# Led_Chaser.net
KiCad netlist of a schematic drawn in Altium Designer
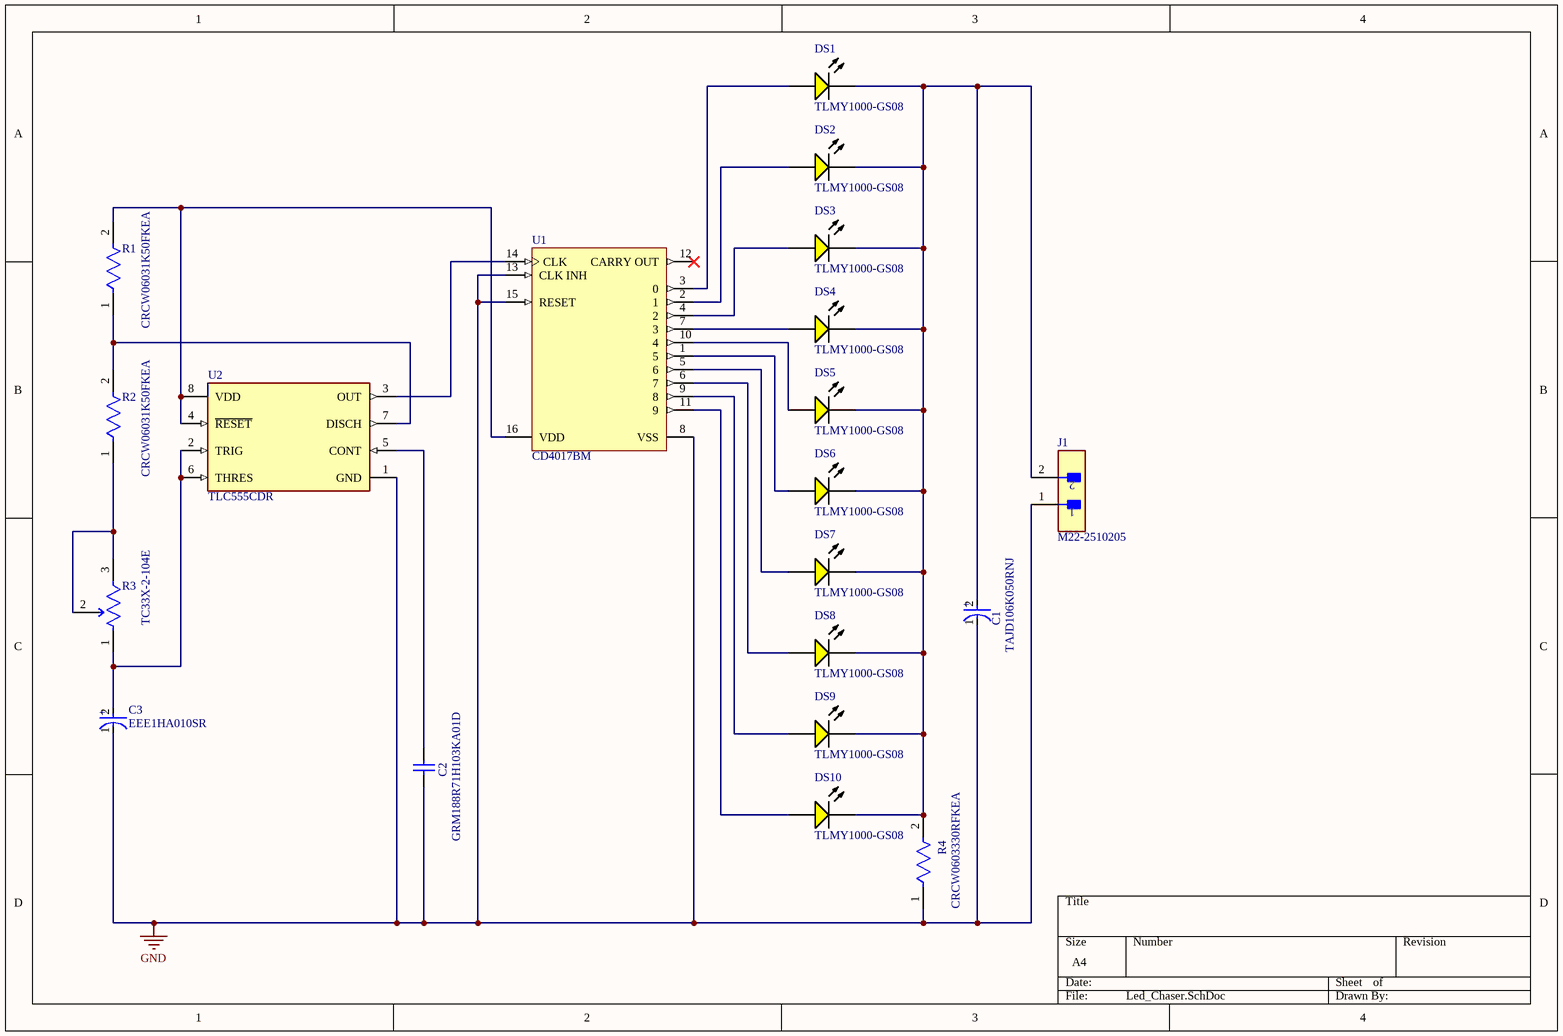
[diagram p0: Led_Chaser.SchDoc]

(export (version "E")
  (design (tool "Eeschema 10.0.6"))
  (components
    (comp (ref "C1")
      (value "TAJD106K050RNJ")
      (footprint "FP-TAJD-MFG")
      (description "10uF 50V  ±10% 800mΩ 2917  SMD Tantalum Capacitor")
      (fields (field (name "VOLTAGE") "50V") (field (name "TOLERANCE") "10%"))
      (libsource (lib "Altium Content Vault") (part "a00bbbee19879c290e62620ae7e47b1"))
    )
    (comp (ref "C2")
      (value "GRM188R71H103KA01D")
      (footprint "CAPC1608X90X35ML10T15")
      (description "Chip Capacitor, 10 nF, +/- 10%, 50 V, -55 to 125 degC, 0603 (1608 Metric), RoHS, Tape and Reel")
      (fields (field (name "VOLTAGE") "50V") (field (name "TOLERANCE") "10%"))
      (libsource (lib "Altium Content Vault") (part "CAP-NP-2"))
    )
    (comp (ref "C3")
      (value "EEE1HA010SR")
      (footprint "FP-SB-MFG")
      (description "CAP ALUM 1UF 20% 50V SMD")
      (fields (field (name "TOLERANCE") "20%") (field (name "VOLTAGE") "50V"))
      (libsource (lib "Altium Content Vault") (part "203bc49f2ac43e59fd269a8c329ed05"))
    )
    (comp (ref "DS1")
      (value "TLMY1000-GS08")
      (footprint "VISH-TLMY1000_V")
      (description "Low Current LED, 40 mW, -40 to 100 degC, 2-Pin SMD, RoHS, Tape and Reel")
      (fields (field (name "MANUFACTURER") "Vishay"))
      (libsource (lib "Altium Content Vault") (part "LED-YELLOW-AK-2"))
    )
    (comp (ref "DS2")
      (value "TLMY1000-GS08")
      (footprint "VISH-TLMY1000_V")
      (description "Low Current LED, 40 mW, -40 to 100 degC, 2-Pin SMD, RoHS, Tape and Reel")
      (fields (field (name "MANUFACTURER") "Vishay"))
      (libsource (lib "Altium Content Vault") (part "LED-YELLOW-AK-2"))
    )
    (comp (ref "DS3")
      (value "TLMY1000-GS08")
      (footprint "VISH-TLMY1000_V")
      (description "Low Current LED, 40 mW, -40 to 100 degC, 2-Pin SMD, RoHS, Tape and Reel")
      (fields (field (name "MANUFACTURER") "Vishay"))
      (libsource (lib "Altium Content Vault") (part "LED-YELLOW-AK-2"))
    )
    (comp (ref "DS4")
      (value "TLMY1000-GS08")
      (footprint "VISH-TLMY1000_V")
      (description "Low Current LED, 40 mW, -40 to 100 degC, 2-Pin SMD, RoHS, Tape and Reel")
      (fields (field (name "MANUFACTURER") "Vishay"))
      (libsource (lib "Altium Content Vault") (part "LED-YELLOW-AK-2"))
    )
    (comp (ref "DS5")
      (value "TLMY1000-GS08")
      (footprint "VISH-TLMY1000_V")
      (description "Low Current LED, 40 mW, -40 to 100 degC, 2-Pin SMD, RoHS, Tape and Reel")
      (fields (field (name "MANUFACTURER") "Vishay"))
      (libsource (lib "Altium Content Vault") (part "LED-YELLOW-AK-2"))
    )
    (comp (ref "DS6")
      (value "TLMY1000-GS08")
      (footprint "VISH-TLMY1000_V")
      (description "Low Current LED, 40 mW, -40 to 100 degC, 2-Pin SMD, RoHS, Tape and Reel")
      (fields (field (name "MANUFACTURER") "Vishay"))
      (libsource (lib "Altium Content Vault") (part "LED-YELLOW-AK-2"))
    )
    (comp (ref "DS7")
      (value "TLMY1000-GS08")
      (footprint "VISH-TLMY1000_V")
      (description "Low Current LED, 40 mW, -40 to 100 degC, 2-Pin SMD, RoHS, Tape and Reel")
      (fields (field (name "MANUFACTURER") "Vishay"))
      (libsource (lib "Altium Content Vault") (part "LED-YELLOW-AK-2"))
    )
    (comp (ref "DS8")
      (value "TLMY1000-GS08")
      (footprint "VISH-TLMY1000_V")
      (description "Low Current LED, 40 mW, -40 to 100 degC, 2-Pin SMD, RoHS, Tape and Reel")
      (fields (field (name "MANUFACTURER") "Vishay"))
      (libsource (lib "Altium Content Vault") (part "LED-YELLOW-AK-2"))
    )
    (comp (ref "DS9")
      (value "TLMY1000-GS08")
      (footprint "VISH-TLMY1000_V")
      (description "Low Current LED, 40 mW, -40 to 100 degC, 2-Pin SMD, RoHS, Tape and Reel")
      (fields (field (name "MANUFACTURER") "Vishay"))
      (libsource (lib "Altium Content Vault") (part "LED-YELLOW-AK-2"))
    )
    (comp (ref "DS10")
      (value "TLMY1000-GS08")
      (footprint "VISH-TLMY1000_V")
      (description "Low Current LED, 40 mW, -40 to 100 degC, 2-Pin SMD, RoHS, Tape and Reel")
      (fields (field (name "MANUFACTURER") "Vishay"))
      (libsource (lib "Altium Content Vault") (part "LED-YELLOW-AK-2"))
    )
    (comp (ref "J1")
      (value "M22-2510205")
      (footprint "FP-M22-2510205-MFG")
      (description "CONN HEADER VERT 2POS 2MM")
      (fields
        (field (name "MANUFACTURER") "Harwin")
        (field (name "OCTOPART") "https://octopart.com/m22-2510205-harwin-2538221")
      )
      (libsource (lib "Altium Content Vault") (part "3bc925449376181038e59eaffc5286c"))
    )
    (comp (ref "R1")
      (value "CRCW06031K50FKEA")
      (footprint "FP-CRCW0603-e3-IPC_A")
      (description "RES Thick Film, 1.5kΩ, 1%, 0.1W, 100ppm/°C, 0603")
      (fields (field (name "TOLERANCE") "1%"))
      (libsource (lib "Altium Content Vault") (part "1029c3af85768c4190bb7ad29bc67b5"))
    )
    (comp (ref "R2")
      (value "CRCW06031K50FKEA")
      (footprint "FP-CRCW0603-e3-IPC_A")
      (description "RES Thick Film, 1.5kΩ, 1%, 0.1W, 100ppm/°C, 0603")
      (fields (field (name "TOLERANCE") "1%"))
      (libsource (lib "Altium Content Vault") (part "1029c3af85768c4190bb7ad29bc67b5"))
    )
    (comp (ref "R3")
      (value "TC33X-2-104E")
      (footprint "FP-TC33X-2-MFG")
      (description "TRIMMER 100K OHM 0.1W J LEAD TOP")
      (fields (field (name "TOLERANCE") "25%"))
      (libsource (lib "Altium Content Vault") (part "13357d81287629c2fd191d242cfa50c"))
    )
    (comp (ref "R4")
      (value "CRCW0603330RFKEA")
      (footprint "FP-CRCW0603-e3-MFG")
      (description "RES Thick Film, 330Ω, 1%, 0.1W, 100ppm/°C, 0603")
      (fields (field (name "TOLERANCE") "1%"))
      (libsource (lib "Altium Content Vault") (part "1029c3af85768c4190bb7ad29bc67b5"))
    )
    (comp (ref "U1")
      (value "CD4017BM")
      (footprint "D0016A_N")
      (description "CMOS Decade Counter with 10 Decoded Outputs, D0016A, TUBE")
      (fields
        (field (name "GENERIC PART NUMBER") "CD4017B")
        (field (name "MANUFACTURER") "Texas Instruments")
      )
      (libsource (lib "Altium Content Vault") (part "TI-CD4017B-16"))
    )
    (comp (ref "U2")
      (value "TLC555CDR")
      (footprint "FP-D0008A-IPC_B")
      (description "IC OSC SGL TIMER 2.1MHZ 8-SOIC")
      (libsource (lib "Altium Content Vault") (part "fd1638d23bf5e420a54176ee4f8e783"))
    )
  )
  (nets
    (net (code "1") (name "GND") (class "Default")
      (node (ref "C1") (pin "1") (pinfunction "C_1") (pintype "passive"))
      (node (ref "C2") (pin "1") (pinfunction "1_1") (pintype "passive"))
      (node (ref "C3") (pin "1") (pinfunction "C_1") (pintype "passive"))
      (node (ref "J1") (pin "1") (pinfunction "1_1") (pintype "passive"))
      (node (ref "R4") (pin "1") (pinfunction "1_1") (pintype "passive"))
      (node (ref "U1") (pin "13") (pinfunction "CLK_INH_13") (pintype "input"))
      (node (ref "U1") (pin "15") (pinfunction "RESET_15") (pintype "input"))
      (node (ref "U1") (pin "8") (pinfunction "VSS_8") (pintype "power_in"))
      (node (ref "U2") (pin "1") (pinfunction "GND_1") (pintype "power_in"))
    )
    (net (code "2") (name "Net-(C1-A)") (class "Default")
      (node (ref "C1") (pin "2") (pinfunction "A_2") (pintype "passive"))
      (node (ref "DS1") (pin "2") (pinfunction "K_2") (pintype "passive"))
      (node (ref "DS10") (pin "2") (pinfunction "K_2") (pintype "passive"))
      (node (ref "DS2") (pin "2") (pinfunction "K_2") (pintype "passive"))
      (node (ref "DS3") (pin "2") (pinfunction "K_2") (pintype "passive"))
      (node (ref "DS4") (pin "2") (pinfunction "K_2") (pintype "passive"))
      (node (ref "DS5") (pin "2") (pinfunction "K_2") (pintype "passive"))
      (node (ref "DS6") (pin "2") (pinfunction "K_2") (pintype "passive"))
      (node (ref "DS7") (pin "2") (pinfunction "K_2") (pintype "passive"))
      (node (ref "DS8") (pin "2") (pinfunction "K_2") (pintype "passive"))
      (node (ref "DS9") (pin "2") (pinfunction "K_2") (pintype "passive"))
      (node (ref "J1") (pin "2") (pinfunction "2_2") (pintype "passive"))
      (node (ref "R4") (pin "2") (pinfunction "2_2") (pintype "passive"))
    )
    (net (code "3") (name "Net-(C3-A)") (class "Default")
      (node (ref "C3") (pin "2") (pinfunction "A_2") (pintype "passive"))
      (node (ref "R3") (pin "1") (pinfunction "CCW_1") (pintype "passive"))
      (node (ref "U2") (pin "2") (pinfunction "TRIG_2") (pintype "input"))
      (node (ref "U2") (pin "6") (pinfunction "THRES_6") (pintype "input"))
    )
    (net (code "4") (name "Net-(DS1-A)") (class "Default")
      (node (ref "DS1") (pin "1") (pinfunction "A_1") (pintype "passive"))
      (node (ref "U1") (pin "3") (pinfunction "0_3") (pintype "output"))
    )
    (net (code "5") (name "Net-(DS2-A)") (class "Default")
      (node (ref "DS2") (pin "1") (pinfunction "A_1") (pintype "passive"))
      (node (ref "U1") (pin "2") (pinfunction "1_2") (pintype "output"))
    )
    (net (code "6") (name "Net-(DS3-A)") (class "Default")
      (node (ref "DS3") (pin "1") (pinfunction "A_1") (pintype "passive"))
      (node (ref "U1") (pin "4") (pinfunction "2_4") (pintype "output"))
    )
    (net (code "7") (name "Net-(DS4-A)") (class "Default")
      (node (ref "DS4") (pin "1") (pinfunction "A_1") (pintype "passive"))
      (node (ref "U1") (pin "7") (pinfunction "3_7") (pintype "output"))
    )
    (net (code "8") (name "Net-(DS5-A)") (class "Default")
      (node (ref "DS5") (pin "1") (pinfunction "A_1") (pintype "passive"))
      (node (ref "U1") (pin "10") (pinfunction "4_10") (pintype "output"))
    )
    (net (code "9") (name "Net-(DS6-A)") (class "Default")
      (node (ref "DS6") (pin "1") (pinfunction "A_1") (pintype "passive"))
      (node (ref "U1") (pin "1") (pinfunction "5_1") (pintype "output"))
    )
    (net (code "10") (name "Net-(DS7-A)") (class "Default")
      (node (ref "DS7") (pin "1") (pinfunction "A_1") (pintype "passive"))
      (node (ref "U1") (pin "5") (pinfunction "6_5") (pintype "output"))
    )
    (net (code "11") (name "Net-(DS8-A)") (class "Default")
      (node (ref "DS8") (pin "1") (pinfunction "A_1") (pintype "passive"))
      (node (ref "U1") (pin "6") (pinfunction "7_6") (pintype "output"))
    )
    (net (code "12") (name "Net-(DS9-A)") (class "Default")
      (node (ref "DS9") (pin "1") (pinfunction "A_1") (pintype "passive"))
      (node (ref "U1") (pin "9") (pinfunction "8_9") (pintype "output"))
    )
    (net (code "13") (name "Net-(DS10-A)") (class "Default")
      (node (ref "DS10") (pin "1") (pinfunction "A_1") (pintype "passive"))
      (node (ref "U1") (pin "11") (pinfunction "9_11") (pintype "output"))
    )
    (net (code "14") (name "Net-(R3-CW)") (class "Default")
      (node (ref "R2") (pin "1") (pinfunction "1_1") (pintype "passive"))
      (node (ref "R3") (pin "2") (pinfunction "WIPER_2") (pintype "passive"))
      (node (ref "R3") (pin "3") (pinfunction "CW_3") (pintype "passive"))
    )
    (net (code "15") (name "Net-(U1-CLK)") (class "Default")
      (node (ref "U1") (pin "14") (pinfunction "CLK_14") (pintype "input"))
      (node (ref "U2") (pin "3") (pinfunction "OUT_3") (pintype "output"))
    )
    (net (code "16") (name "Net-(U1-VDD)") (class "Default")
      (node (ref "R1") (pin "2") (pinfunction "2_2") (pintype "passive"))
      (node (ref "U1") (pin "16") (pinfunction "VDD_16") (pintype "power_in"))
      (node (ref "U2") (pin "4") (pinfunction "~{RESET}_4") (pintype "input"))
      (node (ref "U2") (pin "8") (pinfunction "VDD_8") (pintype "power_in"))
    )
    (net (code "17") (name "Net-(U2-CONT)") (class "Default")
      (node (ref "C2") (pin "2") (pinfunction "2_2") (pintype "passive"))
      (node (ref "U2") (pin "5") (pinfunction "CONT_5") (pintype "input"))
    )
    (net (code "18") (name "Net-(U2-DISCH)") (class "Default")
      (node (ref "R1") (pin "1") (pinfunction "1_1") (pintype "passive"))
      (node (ref "R2") (pin "2") (pinfunction "2_2") (pintype "passive"))
      (node (ref "U2") (pin "7") (pinfunction "DISCH_7") (pintype "output"))
    )
    (net (code "19") (name "unconnected-(U1-CARRY_OUT-Pad12)") (class "Default")
      (node (ref "U1") (pin "12") (pinfunction "CARRY_OUT_12") (pintype "output+no_connect"))
    )
  )
)
